# FPGAPower.net
KiCad netlist of a schematic drawn in Altium Designer
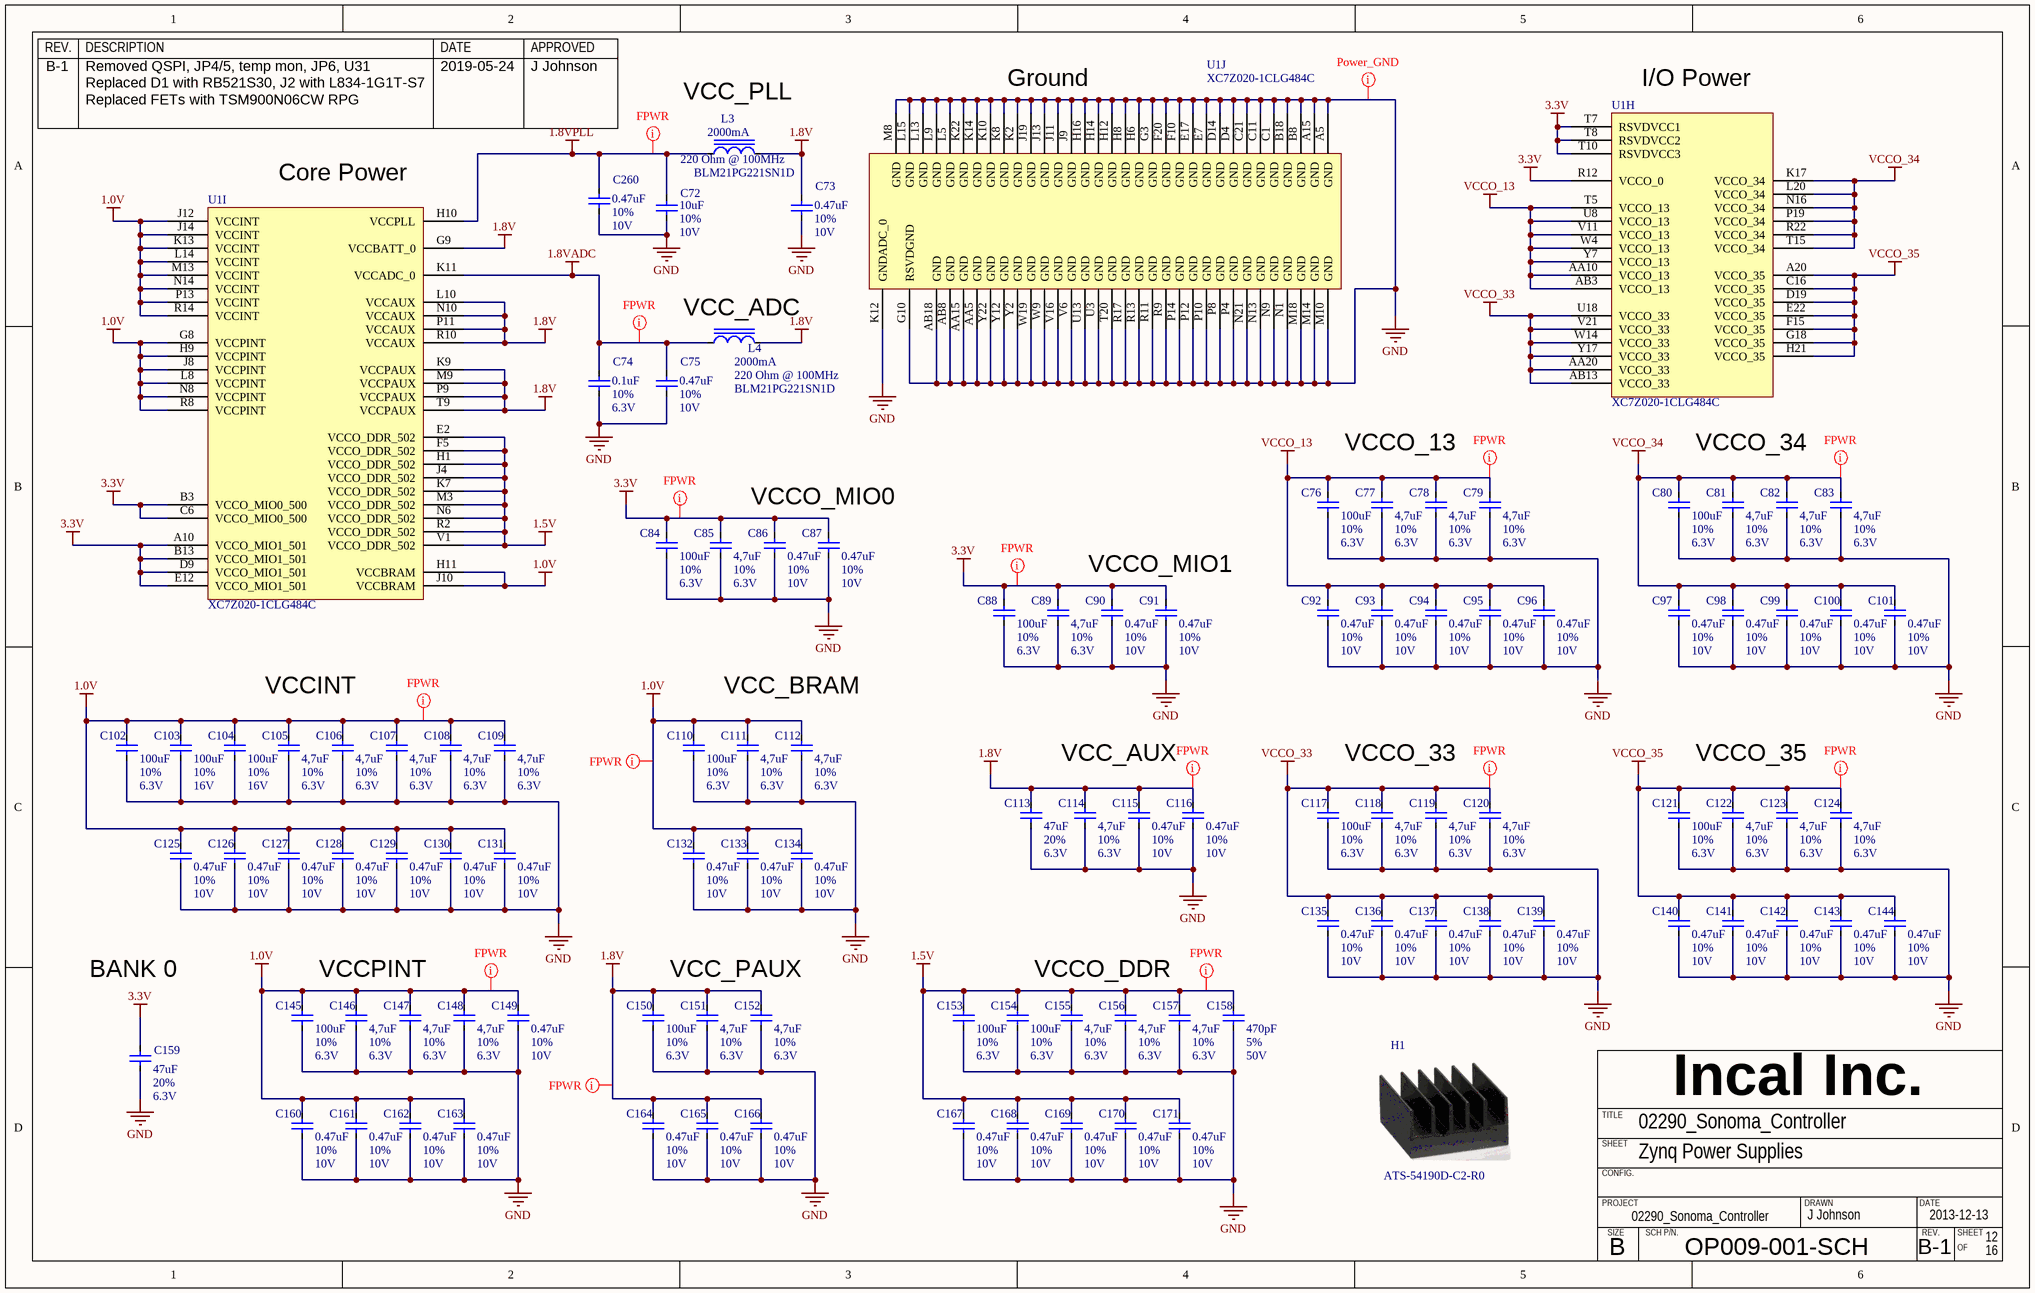
[diagram p0: FPGAPower.SchDoc]

(export (version "E")
  (design (tool "Eeschema 10.0.6"))
  (components
    (comp (ref "C72")
      (value "10uF")
      (footprint "CAPC1608X38N")
      (description "Capacitor ceramic, X5R, 10uF, 10V, 10%, -55 to +85 C, EIA0603")
      (fields
        (field (name "TOLERANCE") "10%")
        (field (name "VOLTAGE") "10V")
        (field (name "Comment") "CAPACITOR_NP_TYPE1")
      )
      (libsource (lib "parts") (part "CAPACITOR_NP_TYPE1"))
    )
    (comp (ref "C73")
      (value "0.47uF")
      (footprint "CAPC1005X55N")
      (description "Capacitor ceramic, X5R, 0.47uF, 10V, 10%, -55 to +85 C, EIA0402")
      (fields
        (field (name "TOLERANCE") "10%")
        (field (name "VOLTAGE") "10V")
        (field (name "Comment") "CAPACITOR_NP_TYPE1")
      )
      (libsource (lib "parts") (part "CAPACITOR_NP_TYPE1"))
    )
    (comp (ref "C74")
      (value "0.1uF")
      (footprint "CAPC0603X33N")
      (description "Capacitor ceramic, X5R, 0.1uF, 6.3V, 10%, -55 to +125 C, EIA0201")
      (fields
        (field (name "TOLERANCE") "10%")
        (field (name "VOLTAGE") "6.3V")
        (field (name "Comment") "CAPACITOR_NP_TYPE1")
      )
      (libsource (lib "parts") (part "CAPACITOR_NP_TYPE1"))
    )
    (comp (ref "C75")
      (value "0.47uF")
      (footprint "CAPC1005X55N")
      (description "Capacitor ceramic, X5R, 0.47uF, 10V, 10%, -55 to +85 C, EIA0402")
      (fields
        (field (name "TOLERANCE") "10%")
        (field (name "VOLTAGE") "10V")
        (field (name "Comment") "CAPACITOR_NP_TYPE1")
      )
      (libsource (lib "parts") (part "CAPACITOR_NP_TYPE1"))
    )
    (comp (ref "C76")
      (value "100uF")
      (footprint "CAPC3225X250N")
      (description "Capacitor ceramic, X5R, 100uF, 6.3V, 10%, -55 to +85 C, EIA1210")
      (fields
        (field (name "TOLERANCE") "10%")
        (field (name "VOLTAGE") "6.3V")
        (field (name "Comment") "CAPACITOR_NP_TYPE1")
      )
      (libsource (lib "parts") (part "CAPACITOR_NP_TYPE1"))
    )
    (comp (ref "C77")
      (value "4,7uF")
      (footprint "CAPC1005X33N")
      (description "Capacitor ceramic, X5R, 4,7uF, 6.3V, 10%, -55 to +85 C, EIA0402")
      (fields
        (field (name "TOLERANCE") "10%")
        (field (name "VOLTAGE") "6.3V")
        (field (name "Comment") "CAPACITOR_NP_TYPE1")
      )
      (libsource (lib "parts") (part "CAPACITOR_NP_TYPE1"))
    )
    (comp (ref "C78")
      (value "4,7uF")
      (footprint "CAPC1005X33N")
      (description "Capacitor ceramic, X5R, 4,7uF, 6.3V, 10%, -55 to +85 C, EIA0402")
      (fields
        (field (name "TOLERANCE") "10%")
        (field (name "VOLTAGE") "6.3V")
        (field (name "Comment") "CAPACITOR_NP_TYPE1")
      )
      (libsource (lib "parts") (part "CAPACITOR_NP_TYPE1"))
    )
    (comp (ref "C79")
      (value "4,7uF")
      (footprint "CAPC1005X33N")
      (description "Capacitor ceramic, X5R, 4,7uF, 6.3V, 10%, -55 to +85 C, EIA0402")
      (fields
        (field (name "TOLERANCE") "10%")
        (field (name "VOLTAGE") "6.3V")
        (field (name "Comment") "CAPACITOR_NP_TYPE1")
      )
      (libsource (lib "parts") (part "CAPACITOR_NP_TYPE1"))
    )
    (comp (ref "C80")
      (value "100uF")
      (footprint "CAPC3225X250N")
      (description "Capacitor ceramic, X5R, 100uF, 6.3V, 10%, -55 to +85 C, EIA1210")
      (fields
        (field (name "TOLERANCE") "10%")
        (field (name "VOLTAGE") "6.3V")
        (field (name "Comment") "CAPACITOR_NP_TYPE1")
      )
      (libsource (lib "parts") (part "CAPACITOR_NP_TYPE1"))
    )
    (comp (ref "C81")
      (value "4,7uF")
      (footprint "CAPC1005X33N")
      (description "Capacitor ceramic, X5R, 4,7uF, 6.3V, 10%, -55 to +85 C, EIA0402")
      (fields
        (field (name "TOLERANCE") "10%")
        (field (name "VOLTAGE") "6.3V")
        (field (name "Comment") "CAPACITOR_NP_TYPE1")
      )
      (libsource (lib "parts") (part "CAPACITOR_NP_TYPE1"))
    )
    (comp (ref "C82")
      (value "4,7uF")
      (footprint "CAPC1005X33N")
      (description "Capacitor ceramic, X5R, 4,7uF, 6.3V, 10%, -55 to +85 C, EIA0402")
      (fields
        (field (name "TOLERANCE") "10%")
        (field (name "VOLTAGE") "6.3V")
        (field (name "Comment") "CAPACITOR_NP_TYPE1")
      )
      (libsource (lib "parts") (part "CAPACITOR_NP_TYPE1"))
    )
    (comp (ref "C83")
      (value "4,7uF")
      (footprint "CAPC1005X33N")
      (description "Capacitor ceramic, X5R, 4,7uF, 6.3V, 10%, -55 to +85 C, EIA0402")
      (fields
        (field (name "TOLERANCE") "10%")
        (field (name "VOLTAGE") "6.3V")
        (field (name "Comment") "CAPACITOR_NP_TYPE1")
      )
      (libsource (lib "parts") (part "CAPACITOR_NP_TYPE1"))
    )
    (comp (ref "C84")
      (value "100uF")
      (footprint "CAPC3225X250N")
      (description "Capacitor ceramic, X5R, 100uF, 6.3V, 10%, -55 to +85 C, EIA1210")
      (fields
        (field (name "TOLERANCE") "10%")
        (field (name "VOLTAGE") "6.3V")
        (field (name "Comment") "CAPACITOR_NP_TYPE1")
      )
      (libsource (lib "parts") (part "CAPACITOR_NP_TYPE1"))
    )
    (comp (ref "C85")
      (value "4,7uF")
      (footprint "CAPC1005X33N")
      (description "Capacitor ceramic, X5R, 4,7uF, 6.3V, 10%, -55 to +85 C, EIA0402")
      (fields
        (field (name "TOLERANCE") "10%")
        (field (name "VOLTAGE") "6.3V")
        (field (name "Comment") "CAPACITOR_NP_TYPE1")
      )
      (libsource (lib "parts") (part "CAPACITOR_NP_TYPE1"))
    )
    (comp (ref "C86")
      (value "0.47uF")
      (footprint "CAPC1005X55N")
      (description "Capacitor ceramic, X5R, 0.47uF, 10V, 10%, -55 to +85 C, EIA0402")
      (fields
        (field (name "TOLERANCE") "10%")
        (field (name "VOLTAGE") "10V")
        (field (name "Comment") "CAPACITOR_NP_TYPE1")
      )
      (libsource (lib "parts") (part "CAPACITOR_NP_TYPE1"))
    )
    (comp (ref "C87")
      (value "0.47uF")
      (footprint "CAPC1005X55N")
      (description "Capacitor ceramic, X5R, 0.47uF, 10V, 10%, -55 to +85 C, EIA0402")
      (fields
        (field (name "TOLERANCE") "10%")
        (field (name "VOLTAGE") "10V")
        (field (name "Comment") "CAPACITOR_NP_TYPE1")
      )
      (libsource (lib "parts") (part "CAPACITOR_NP_TYPE1"))
    )
    (comp (ref "C88")
      (value "100uF")
      (footprint "CAPC3225X250N")
      (description "Capacitor ceramic, X5R, 100uF, 6.3V, 10%, -55 to +85 C, EIA1210")
      (fields
        (field (name "TOLERANCE") "10%")
        (field (name "VOLTAGE") "6.3V")
        (field (name "Comment") "CAPACITOR_NP_TYPE1")
      )
      (libsource (lib "parts") (part "CAPACITOR_NP_TYPE1"))
    )
    (comp (ref "C89")
      (value "4,7uF")
      (footprint "CAPC1005X33N")
      (description "Capacitor ceramic, X5R, 4,7uF, 6.3V, 10%, -55 to +85 C, EIA0402")
      (fields
        (field (name "TOLERANCE") "10%")
        (field (name "VOLTAGE") "6.3V")
        (field (name "Comment") "CAPACITOR_NP_TYPE1")
      )
      (libsource (lib "parts") (part "CAPACITOR_NP_TYPE1"))
    )
    (comp (ref "C90")
      (value "0.47uF")
      (footprint "CAPC1005X55N")
      (description "Capacitor ceramic, X5R, 0.47uF, 10V, 10%, -55 to +85 C, EIA0402")
      (fields
        (field (name "TOLERANCE") "10%")
        (field (name "VOLTAGE") "10V")
        (field (name "Comment") "CAPACITOR_NP_TYPE1")
      )
      (libsource (lib "parts") (part "CAPACITOR_NP_TYPE1"))
    )
    (comp (ref "C91")
      (value "0.47uF")
      (footprint "CAPC1005X55N")
      (description "Capacitor ceramic, X5R, 0.47uF, 10V, 10%, -55 to +85 C, EIA0402")
      (fields
        (field (name "TOLERANCE") "10%")
        (field (name "VOLTAGE") "10V")
        (field (name "Comment") "CAPACITOR_NP_TYPE1")
      )
      (libsource (lib "parts") (part "CAPACITOR_NP_TYPE1"))
    )
    (comp (ref "C92")
      (value "0.47uF")
      (footprint "CAPC1005X55N")
      (description "Capacitor ceramic, X5R, 0.47uF, 10V, 10%, -55 to +85 C, EIA0402")
      (fields
        (field (name "TOLERANCE") "10%")
        (field (name "VOLTAGE") "10V")
        (field (name "Comment") "CAPACITOR_NP_TYPE1")
      )
      (libsource (lib "parts") (part "CAPACITOR_NP_TYPE1"))
    )
    (comp (ref "C93")
      (value "0.47uF")
      (footprint "CAPC1005X55N")
      (description "Capacitor ceramic, X5R, 0.47uF, 10V, 10%, -55 to +85 C, EIA0402")
      (fields
        (field (name "TOLERANCE") "10%")
        (field (name "VOLTAGE") "10V")
        (field (name "Comment") "CAPACITOR_NP_TYPE1")
      )
      (libsource (lib "parts") (part "CAPACITOR_NP_TYPE1"))
    )
    (comp (ref "C94")
      (value "0.47uF")
      (footprint "CAPC1005X55N")
      (description "Capacitor ceramic, X5R, 0.47uF, 10V, 10%, -55 to +85 C, EIA0402")
      (fields
        (field (name "TOLERANCE") "10%")
        (field (name "VOLTAGE") "10V")
        (field (name "Comment") "CAPACITOR_NP_TYPE1")
      )
      (libsource (lib "parts") (part "CAPACITOR_NP_TYPE1"))
    )
    (comp (ref "C95")
      (value "0.47uF")
      (footprint "CAPC1005X55N")
      (description "Capacitor ceramic, X5R, 0.47uF, 10V, 10%, -55 to +85 C, EIA0402")
      (fields
        (field (name "TOLERANCE") "10%")
        (field (name "VOLTAGE") "10V")
        (field (name "Comment") "CAPACITOR_NP_TYPE1")
      )
      (libsource (lib "parts") (part "CAPACITOR_NP_TYPE1"))
    )
    (comp (ref "C96")
      (value "0.47uF")
      (footprint "CAPC1005X55N")
      (description "Capacitor ceramic, X5R, 0.47uF, 10V, 10%, -55 to +85 C, EIA0402")
      (fields
        (field (name "TOLERANCE") "10%")
        (field (name "VOLTAGE") "10V")
        (field (name "Comment") "CAPACITOR_NP_TYPE1")
      )
      (libsource (lib "parts") (part "CAPACITOR_NP_TYPE1"))
    )
    (comp (ref "C97")
      (value "0.47uF")
      (footprint "CAPC1005X55N")
      (description "Capacitor ceramic, X5R, 0.47uF, 10V, 10%, -55 to +85 C, EIA0402")
      (fields
        (field (name "TOLERANCE") "10%")
        (field (name "VOLTAGE") "10V")
        (field (name "Comment") "CAPACITOR_NP_TYPE1")
      )
      (libsource (lib "parts") (part "CAPACITOR_NP_TYPE1"))
    )
    (comp (ref "C98")
      (value "0.47uF")
      (footprint "CAPC1005X55N")
      (description "Capacitor ceramic, X5R, 0.47uF, 10V, 10%, -55 to +85 C, EIA0402")
      (fields
        (field (name "TOLERANCE") "10%")
        (field (name "VOLTAGE") "10V")
        (field (name "Comment") "CAPACITOR_NP_TYPE1")
      )
      (libsource (lib "parts") (part "CAPACITOR_NP_TYPE1"))
    )
    (comp (ref "C99")
      (value "0.47uF")
      (footprint "CAPC1005X55N")
      (description "Capacitor ceramic, X5R, 0.47uF, 10V, 10%, -55 to +85 C, EIA0402")
      (fields
        (field (name "TOLERANCE") "10%")
        (field (name "VOLTAGE") "10V")
        (field (name "Comment") "CAPACITOR_NP_TYPE1")
      )
      (libsource (lib "parts") (part "CAPACITOR_NP_TYPE1"))
    )
    (comp (ref "C100")
      (value "0.47uF")
      (footprint "CAPC1005X55N")
      (description "Capacitor ceramic, X5R, 0.47uF, 10V, 10%, -55 to +85 C, EIA0402")
      (fields
        (field (name "TOLERANCE") "10%")
        (field (name "VOLTAGE") "10V")
        (field (name "Comment") "CAPACITOR_NP_TYPE1")
      )
      (libsource (lib "parts") (part "CAPACITOR_NP_TYPE1"))
    )
    (comp (ref "C101")
      (value "0.47uF")
      (footprint "CAPC1005X55N")
      (description "Capacitor ceramic, X5R, 0.47uF, 10V, 10%, -55 to +85 C, EIA0402")
      (fields
        (field (name "TOLERANCE") "10%")
        (field (name "VOLTAGE") "10V")
        (field (name "Comment") "CAPACITOR_NP_TYPE1")
      )
      (libsource (lib "parts") (part "CAPACITOR_NP_TYPE1"))
    )
    (comp (ref "C102")
      (value "100uF")
      (footprint "CAPC3225X250N")
      (description "Capacitor ceramic, X5R, 100uF, 6.3V, 10%, -55 to +85 C, EIA1210")
      (fields
        (field (name "TOLERANCE") "10%")
        (field (name "VOLTAGE") "6.3V")
        (field (name "Comment") "CAPACITOR_NP_TYPE1")
      )
      (libsource (lib "parts") (part "CAPACITOR_NP_TYPE1"))
    )
    (comp (ref "C103")
      (value "100uF")
      (footprint "CAPC3225X250N")
      (description "Capacitor ceramic, X5R, 100uF, 16V, 10%, -55 to +85 C, EIA1210")
      (fields
        (field (name "TOLERANCE") "10%")
        (field (name "VOLTAGE") "16V")
        (field (name "Comment") "CAPACITOR_NP_TYPE1")
      )
      (libsource (lib "parts") (part "CAPACITOR_NP_TYPE1"))
    )
    (comp (ref "C104")
      (value "100uF")
      (footprint "CAPC3225X250N")
      (description "Capacitor ceramic, X5R, 100uF, 16V, 10%, -55 to +85 C, EIA1210")
      (fields
        (field (name "TOLERANCE") "10%")
        (field (name "VOLTAGE") "16V")
        (field (name "Comment") "CAPACITOR_NP_TYPE1")
      )
      (libsource (lib "parts") (part "CAPACITOR_NP_TYPE1"))
    )
    (comp (ref "C105")
      (value "4,7uF")
      (footprint "CAPC1005X33N")
      (description "Capacitor ceramic, X5R, 4,7uF, 6.3V, 10%, -55 to +85 C, EIA0402")
      (fields
        (field (name "TOLERANCE") "10%")
        (field (name "VOLTAGE") "6.3V")
        (field (name "Comment") "CAPACITOR_NP_TYPE1")
      )
      (libsource (lib "parts") (part "CAPACITOR_NP_TYPE1"))
    )
    (comp (ref "C106")
      (value "4,7uF")
      (footprint "CAPC1005X33N")
      (description "Capacitor ceramic, X5R, 4,7uF, 6.3V, 10%, -55 to +85 C, EIA0402")
      (fields
        (field (name "TOLERANCE") "10%")
        (field (name "VOLTAGE") "6.3V")
        (field (name "Comment") "CAPACITOR_NP_TYPE1")
      )
      (libsource (lib "parts") (part "CAPACITOR_NP_TYPE1"))
    )
    (comp (ref "C107")
      (value "4,7uF")
      (footprint "CAPC1005X33N")
      (description "Capacitor ceramic, X5R, 4,7uF, 6.3V, 10%, -55 to +85 C, EIA0402")
      (fields
        (field (name "TOLERANCE") "10%")
        (field (name "VOLTAGE") "6.3V")
        (field (name "Comment") "CAPACITOR_NP_TYPE1")
      )
      (libsource (lib "parts") (part "CAPACITOR_NP_TYPE1"))
    )
    (comp (ref "C108")
      (value "4,7uF")
      (footprint "CAPC1005X33N")
      (description "Capacitor ceramic, X5R, 4,7uF, 6.3V, 10%, -55 to +85 C, EIA0402")
      (fields
        (field (name "TOLERANCE") "10%")
        (field (name "VOLTAGE") "6.3V")
        (field (name "Comment") "CAPACITOR_NP_TYPE1")
      )
      (libsource (lib "parts") (part "CAPACITOR_NP_TYPE1"))
    )
    (comp (ref "C109")
      (value "4,7uF")
      (footprint "CAPC1005X33N")
      (description "Capacitor ceramic, X5R, 4,7uF, 6.3V, 10%, -55 to +85 C, EIA0402")
      (fields
        (field (name "TOLERANCE") "10%")
        (field (name "VOLTAGE") "6.3V")
        (field (name "Comment") "CAPACITOR_NP_TYPE1")
      )
      (libsource (lib "parts") (part "CAPACITOR_NP_TYPE1"))
    )
    (comp (ref "C110")
      (value "100uF")
      (footprint "CAPC3225X250N")
      (description "Capacitor ceramic, X5R, 100uF, 6.3V, 10%, -55 to +85 C, EIA1210")
      (fields
        (field (name "TOLERANCE") "10%")
        (field (name "VOLTAGE") "6.3V")
        (field (name "Comment") "CAPACITOR_NP_TYPE1")
      )
      (libsource (lib "parts") (part "CAPACITOR_NP_TYPE1"))
    )
    (comp (ref "C111")
      (value "4,7uF")
      (footprint "CAPC1005X33N")
      (description "Capacitor ceramic, X5R, 4,7uF, 6.3V, 10%, -55 to +85 C, EIA0402")
      (fields
        (field (name "TOLERANCE") "10%")
        (field (name "VOLTAGE") "6.3V")
        (field (name "Comment") "CAPACITOR_NP_TYPE1")
      )
      (libsource (lib "parts") (part "CAPACITOR_NP_TYPE1"))
    )
    (comp (ref "C112")
      (value "4,7uF")
      (footprint "CAPC1005X33N")
      (description "Capacitor ceramic, X5R, 4,7uF, 6.3V, 10%, -55 to +85 C, EIA0402")
      (fields
        (field (name "TOLERANCE") "10%")
        (field (name "VOLTAGE") "6.3V")
        (field (name "Comment") "CAPACITOR_NP_TYPE1")
      )
      (libsource (lib "parts") (part "CAPACITOR_NP_TYPE1"))
    )
    (comp (ref "C113")
      (value "47uF")
      (footprint "CAPC2013X125N")
      (description "Capacitor ceramic, X5R, 47uF, 6.3V, 20%, -55 to +85 C,")
      (fields
        (field (name "TOLERANCE") "20%")
        (field (name "VOLTAGE") "6.3V")
        (field (name "Comment") "CAPACITOR_NP_TYPE1")
      )
      (libsource (lib "parts") (part "CAPACITOR_NP_TYPE1"))
    )
    (comp (ref "C114")
      (value "4,7uF")
      (footprint "CAPC1005X33N")
      (description "Capacitor ceramic, X5R, 4,7uF, 6.3V, 10%, -55 to +85 C, EIA0402")
      (fields
        (field (name "TOLERANCE") "10%")
        (field (name "VOLTAGE") "6.3V")
        (field (name "Comment") "CAPACITOR_NP_TYPE1")
      )
      (libsource (lib "parts") (part "CAPACITOR_NP_TYPE1"))
    )
    (comp (ref "C115")
      (value "0.47uF")
      (footprint "CAPC1005X55N")
      (description "Capacitor ceramic, X5R, 0.47uF, 10V, 10%, -55 to +85 C, EIA0402")
      (fields
        (field (name "TOLERANCE") "10%")
        (field (name "VOLTAGE") "10V")
        (field (name "Comment") "CAPACITOR_NP_TYPE1")
      )
      (libsource (lib "parts") (part "CAPACITOR_NP_TYPE1"))
    )
    (comp (ref "C116")
      (value "0.47uF")
      (footprint "CAPC1005X55N")
      (description "Capacitor ceramic, X5R, 0.47uF, 10V, 10%, -55 to +85 C, EIA0402")
      (fields
        (field (name "TOLERANCE") "10%")
        (field (name "VOLTAGE") "10V")
        (field (name "Comment") "CAPACITOR_NP_TYPE1")
      )
      (libsource (lib "parts") (part "CAPACITOR_NP_TYPE1"))
    )
    (comp (ref "C117")
      (value "100uF")
      (footprint "CAPC3225X250N")
      (description "Capacitor ceramic, X5R, 100uF, 6.3V, 10%, -55 to +85 C, EIA1210")
      (fields
        (field (name "TOLERANCE") "10%")
        (field (name "VOLTAGE") "6.3V")
        (field (name "Comment") "CAPACITOR_NP_TYPE1")
      )
      (libsource (lib "parts") (part "CAPACITOR_NP_TYPE1"))
    )
    (comp (ref "C118")
      (value "4,7uF")
      (footprint "CAPC1005X33N")
      (description "Capacitor ceramic, X5R, 4,7uF, 6.3V, 10%, -55 to +85 C, EIA0402")
      (fields
        (field (name "TOLERANCE") "10%")
        (field (name "VOLTAGE") "6.3V")
        (field (name "Comment") "CAPACITOR_NP_TYPE1")
      )
      (libsource (lib "parts") (part "CAPACITOR_NP_TYPE1"))
    )
    (comp (ref "C119")
      (value "4,7uF")
      (footprint "CAPC1005X33N")
      (description "Capacitor ceramic, X5R, 4,7uF, 6.3V, 10%, -55 to +85 C, EIA0402")
      (fields
        (field (name "TOLERANCE") "10%")
        (field (name "VOLTAGE") "6.3V")
        (field (name "Comment") "CAPACITOR_NP_TYPE1")
      )
      (libsource (lib "parts") (part "CAPACITOR_NP_TYPE1"))
    )
    (comp (ref "C120")
      (value "4,7uF")
      (footprint "CAPC1005X33N")
      (description "Capacitor ceramic, X5R, 4,7uF, 6.3V, 10%, -55 to +85 C, EIA0402")
      (fields
        (field (name "TOLERANCE") "10%")
        (field (name "VOLTAGE") "6.3V")
        (field (name "Comment") "CAPACITOR_NP_TYPE1")
      )
      (libsource (lib "parts") (part "CAPACITOR_NP_TYPE1"))
    )
    (comp (ref "C121")
      (value "100uF")
      (footprint "CAPC3225X250N")
      (description "Capacitor ceramic, X5R, 100uF, 6.3V, 10%, -55 to +85 C, EIA1210")
      (fields
        (field (name "TOLERANCE") "10%")
        (field (name "VOLTAGE") "6.3V")
        (field (name "Comment") "CAPACITOR_NP_TYPE1")
      )
      (libsource (lib "parts") (part "CAPACITOR_NP_TYPE1"))
    )
    (comp (ref "C122")
      (value "4,7uF")
      (footprint "CAPC1005X33N")
      (description "Capacitor ceramic, X5R, 4,7uF, 6.3V, 10%, -55 to +85 C, EIA0402")
      (fields
        (field (name "TOLERANCE") "10%")
        (field (name "VOLTAGE") "6.3V")
        (field (name "Comment") "CAPACITOR_NP_TYPE1")
      )
      (libsource (lib "parts") (part "CAPACITOR_NP_TYPE1"))
    )
    (comp (ref "C123")
      (value "4,7uF")
      (footprint "CAPC1005X33N")
      (description "Capacitor ceramic, X5R, 4,7uF, 6.3V, 10%, -55 to +85 C, EIA0402")
      (fields
        (field (name "TOLERANCE") "10%")
        (field (name "VOLTAGE") "6.3V")
        (field (name "Comment") "CAPACITOR_NP_TYPE1")
      )
      (libsource (lib "parts") (part "CAPACITOR_NP_TYPE1"))
    )
    (comp (ref "C124")
      (value "4,7uF")
      (footprint "CAPC1005X33N")
      (description "Capacitor ceramic, X5R, 4,7uF, 6.3V, 10%, -55 to +85 C, EIA0402")
      (fields
        (field (name "TOLERANCE") "10%")
        (field (name "VOLTAGE") "6.3V")
        (field (name "Comment") "CAPACITOR_NP_TYPE1")
      )
      (libsource (lib "parts") (part "CAPACITOR_NP_TYPE1"))
    )
    (comp (ref "C125")
      (value "0.47uF")
      (footprint "CAPC1005X55N")
      (description "Capacitor ceramic, X5R, 0.47uF, 10V, 10%, -55 to +85 C, EIA0402")
      (fields
        (field (name "TOLERANCE") "10%")
        (field (name "VOLTAGE") "10V")
        (field (name "Comment") "CAPACITOR_NP_TYPE1")
      )
      (libsource (lib "parts") (part "CAPACITOR_NP_TYPE1"))
    )
    (comp (ref "C126")
      (value "0.47uF")
      (footprint "CAPC1005X55N")
      (description "Capacitor ceramic, X5R, 0.47uF, 10V, 10%, -55 to +85 C, EIA0402")
      (fields
        (field (name "TOLERANCE") "10%")
        (field (name "VOLTAGE") "10V")
        (field (name "Comment") "CAPACITOR_NP_TYPE1")
      )
      (libsource (lib "parts") (part "CAPACITOR_NP_TYPE1"))
    )
    (comp (ref "C127")
      (value "0.47uF")
      (footprint "CAPC1005X55N")
      (description "Capacitor ceramic, X5R, 0.47uF, 10V, 10%, -55 to +85 C, EIA0402")
      (fields
        (field (name "TOLERANCE") "10%")
        (field (name "VOLTAGE") "10V")
        (field (name "Comment") "CAPACITOR_NP_TYPE1")
      )
      (libsource (lib "parts") (part "CAPACITOR_NP_TYPE1"))
    )
    (comp (ref "C128")
      (value "0.47uF")
      (footprint "CAPC1005X55N")
      (description "Capacitor ceramic, X5R, 0.47uF, 10V, 10%, -55 to +85 C, EIA0402")
      (fields
        (field (name "TOLERANCE") "10%")
        (field (name "VOLTAGE") "10V")
        (field (name "Comment") "CAPACITOR_NP_TYPE1")
      )
      (libsource (lib "parts") (part "CAPACITOR_NP_TYPE1"))
    )
    (comp (ref "C129")
      (value "0.47uF")
      (footprint "CAPC1005X55N")
      (description "Capacitor ceramic, X5R, 0.47uF, 10V, 10%, -55 to +85 C, EIA0402")
      (fields
        (field (name "TOLERANCE") "10%")
        (field (name "VOLTAGE") "10V")
        (field (name "Comment") "CAPACITOR_NP_TYPE1")
      )
      (libsource (lib "parts") (part "CAPACITOR_NP_TYPE1"))
    )
    (comp (ref "C130")
      (value "0.47uF")
      (footprint "CAPC1005X55N")
      (description "Capacitor ceramic, X5R, 0.47uF, 10V, 10%, -55 to +85 C, EIA0402")
      (fields
        (field (name "TOLERANCE") "10%")
        (field (name "VOLTAGE") "10V")
        (field (name "Comment") "CAPACITOR_NP_TYPE1")
      )
      (libsource (lib "parts") (part "CAPACITOR_NP_TYPE1"))
    )
    (comp (ref "C131")
      (value "0.47uF")
      (footprint "CAPC1005X55N")
      (description "Capacitor ceramic, X5R, 0.47uF, 10V, 10%, -55 to +85 C, EIA0402")
      (fields
        (field (name "TOLERANCE") "10%")
        (field (name "VOLTAGE") "10V")
        (field (name "Comment") "CAPACITOR_NP_TYPE1")
      )
      (libsource (lib "parts") (part "CAPACITOR_NP_TYPE1"))
    )
    (comp (ref "C132")
      (value "0.47uF")
      (footprint "CAPC1005X55N")
      (description "Capacitor ceramic, X5R, 0.47uF, 10V, 10%, -55 to +85 C, EIA0402")
      (fields
        (field (name "TOLERANCE") "10%")
        (field (name "VOLTAGE") "10V")
        (field (name "Comment") "CAPACITOR_NP_TYPE1")
      )
      (libsource (lib "parts") (part "CAPACITOR_NP_TYPE1"))
    )
    (comp (ref "C133")
      (value "0.47uF")
      (footprint "CAPC1005X55N")
      (description "Capacitor ceramic, X5R, 0.47uF, 10V, 10%, -55 to +85 C, EIA0402")
      (fields
        (field (name "TOLERANCE") "10%")
        (field (name "VOLTAGE") "10V")
        (field (name "Comment") "CAPACITOR_NP_TYPE1")
      )
      (libsource (lib "parts") (part "CAPACITOR_NP_TYPE1"))
    )
    (comp (ref "C134")
      (value "0.47uF")
      (footprint "CAPC1005X55N")
      (description "Capacitor ceramic, X5R, 0.47uF, 10V, 10%, -55 to +85 C, EIA0402")
      (fields
        (field (name "TOLERANCE") "10%")
        (field (name "VOLTAGE") "10V")
        (field (name "Comment") "CAPACITOR_NP_TYPE1")
      )
      (libsource (lib "parts") (part "CAPACITOR_NP_TYPE1"))
    )
    (comp (ref "C135")
      (value "0.47uF")
      (footprint "CAPC1005X55N")
      (description "Capacitor ceramic, X5R, 0.47uF, 10V, 10%, -55 to +85 C, EIA0402")
      (fields
        (field (name "TOLERANCE") "10%")
        (field (name "VOLTAGE") "10V")
        (field (name "Comment") "CAPACITOR_NP_TYPE1")
      )
      (libsource (lib "parts") (part "CAPACITOR_NP_TYPE1"))
    )
    (comp (ref "C136")
      (value "0.47uF")
      (footprint "CAPC1005X55N")
      (description "Capacitor ceramic, X5R, 0.47uF, 10V, 10%, -55 to +85 C, EIA0402")
      (fields
        (field (name "TOLERANCE") "10%")
        (field (name "VOLTAGE") "10V")
        (field (name "Comment") "CAPACITOR_NP_TYPE1")
      )
      (libsource (lib "parts") (part "CAPACITOR_NP_TYPE1"))
    )
    (comp (ref "C137")
      (value "0.47uF")
      (footprint "CAPC1005X55N")
      (description "Capacitor ceramic, X5R, 0.47uF, 10V, 10%, -55 to +85 C, EIA0402")
      (fields
        (field (name "TOLERANCE") "10%")
        (field (name "VOLTAGE") "10V")
        (field (name "Comment") "CAPACITOR_NP_TYPE1")
      )
      (libsource (lib "parts") (part "CAPACITOR_NP_TYPE1"))
    )
    (comp (ref "C138")
      (value "0.47uF")
      (footprint "CAPC1005X55N")
      (description "Capacitor ceramic, X5R, 0.47uF, 10V, 10%, -55 to +85 C, EIA0402")
      (fields
        (field (name "TOLERANCE") "10%")
        (field (name "VOLTAGE") "10V")
        (field (name "Comment") "CAPACITOR_NP_TYPE1")
      )
      (libsource (lib "parts") (part "CAPACITOR_NP_TYPE1"))
    )
    (comp (ref "C139")
      (value "0.47uF")
      (footprint "CAPC1005X55N")
      (description "Capacitor ceramic, X5R, 0.47uF, 10V, 10%, -55 to +85 C, EIA0402")
      (fields
        (field (name "TOLERANCE") "10%")
        (field (name "VOLTAGE") "10V")
        (field (name "Comment") "CAPACITOR_NP_TYPE1")
      )
      (libsource (lib "parts") (part "CAPACITOR_NP_TYPE1"))
    )
    (comp (ref "C140")
      (value "0.47uF")
      (footprint "CAPC1005X55N")
      (description "Capacitor ceramic, X5R, 0.47uF, 10V, 10%, -55 to +85 C, EIA0402")
      (fields
        (field (name "TOLERANCE") "10%")
        (field (name "VOLTAGE") "10V")
        (field (name "Comment") "CAPACITOR_NP_TYPE1")
      )
      (libsource (lib "parts") (part "CAPACITOR_NP_TYPE1"))
    )
    (comp (ref "C141")
      (value "0.47uF")
      (footprint "CAPC1005X55N")
      (description "Capacitor ceramic, X5R, 0.47uF, 10V, 10%, -55 to +85 C, EIA0402")
      (fields
        (field (name "TOLERANCE") "10%")
        (field (name "VOLTAGE") "10V")
        (field (name "Comment") "CAPACITOR_NP_TYPE1")
      )
      (libsource (lib "parts") (part "CAPACITOR_NP_TYPE1"))
    )
    (comp (ref "C142")
      (value "0.47uF")
      (footprint "CAPC1005X55N")
      (description "Capacitor ceramic, X5R, 0.47uF, 10V, 10%, -55 to +85 C, EIA0402")
      (fields
        (field (name "TOLERANCE") "10%")
        (field (name "VOLTAGE") "10V")
        (field (name "Comment") "CAPACITOR_NP_TYPE1")
      )
      (libsource (lib "parts") (part "CAPACITOR_NP_TYPE1"))
    )
    (comp (ref "C143")
      (value "0.47uF")
      (footprint "CAPC1005X55N")
      (description "Capacitor ceramic, X5R, 0.47uF, 10V, 10%, -55 to +85 C, EIA0402")
      (fields
        (field (name "TOLERANCE") "10%")
        (field (name "VOLTAGE") "10V")
        (field (name "Comment") "CAPACITOR_NP_TYPE1")
      )
      (libsource (lib "parts") (part "CAPACITOR_NP_TYPE1"))
    )
    (comp (ref "C144")
      (value "0.47uF")
      (footprint "CAPC1005X55N")
      (description "Capacitor ceramic, X5R, 0.47uF, 10V, 10%, -55 to +85 C, EIA0402")
      (fields
        (field (name "TOLERANCE") "10%")
        (field (name "VOLTAGE") "10V")
        (field (name "Comment") "CAPACITOR_NP_TYPE1")
      )
      (libsource (lib "parts") (part "CAPACITOR_NP_TYPE1"))
    )
    (comp (ref "C145")
      (value "100uF")
      (footprint "CAPC3225X250N")
      (description "Capacitor ceramic, X5R, 100uF, 6.3V, 10%, -55 to +85 C, EIA1210")
      (fields
        (field (name "TOLERANCE") "10%")
        (field (name "VOLTAGE") "6.3V")
        (field (name "Comment") "CAPACITOR_NP_TYPE1")
      )
      (libsource (lib "parts") (part "CAPACITOR_NP_TYPE1"))
    )
    (comp (ref "C146")
      (value "4,7uF")
      (footprint "CAPC1005X33N")
      (description "Capacitor ceramic, X5R, 4,7uF, 6.3V, 10%, -55 to +85 C, EIA0402")
      (fields
        (field (name "TOLERANCE") "10%")
        (field (name "VOLTAGE") "6.3V")
        (field (name "Comment") "CAPACITOR_NP_TYPE1")
      )
      (libsource (lib "parts") (part "CAPACITOR_NP_TYPE1"))
    )
    (comp (ref "C147")
      (value "4,7uF")
      (footprint "CAPC1005X33N")
      (description "Capacitor ceramic, X5R, 4,7uF, 6.3V, 10%, -55 to +85 C, EIA0402")
      (fields
        (field (name "TOLERANCE") "10%")
        (field (name "VOLTAGE") "6.3V")
        (field (name "Comment") "CAPACITOR_NP_TYPE1")
      )
      (libsource (lib "parts") (part "CAPACITOR_NP_TYPE1"))
    )
    (comp (ref "C148")
      (value "4,7uF")
      (footprint "CAPC1005X33N")
      (description "Capacitor ceramic, X5R, 4,7uF, 6.3V, 10%, -55 to +85 C, EIA0402")
      (fields
        (field (name "TOLERANCE") "10%")
        (field (name "VOLTAGE") "6.3V")
        (field (name "Comment") "CAPACITOR_NP_TYPE1")
      )
      (libsource (lib "parts") (part "CAPACITOR_NP_TYPE1"))
    )
    (comp (ref "C149")
      (value "0.47uF")
      (footprint "CAPC1005X55N")
      (description "Capacitor ceramic, X5R, 0.47uF, 10V, 10%, -55 to +85 C, EIA0402")
      (fields
        (field (name "TOLERANCE") "10%")
        (field (name "VOLTAGE") "10V")
        (field (name "Comment") "CAPACITOR_NP_TYPE1")
      )
      (libsource (lib "parts") (part "CAPACITOR_NP_TYPE1"))
    )
    (comp (ref "C150")
      (value "100uF")
      (footprint "CAPC3225X250N")
      (description "Capacitor ceramic, X5R, 100uF, 6.3V, 10%, -55 to +85 C, EIA1210")
      (fields
        (field (name "TOLERANCE") "10%")
        (field (name "VOLTAGE") "6.3V")
        (field (name "Comment") "CAPACITOR_NP_TYPE1")
      )
      (libsource (lib "parts") (part "CAPACITOR_NP_TYPE1"))
    )
    (comp (ref "C151")
      (value "4,7uF")
      (footprint "CAPC1005X33N")
      (description "Capacitor ceramic, X5R, 4,7uF, 6.3V, 10%, -55 to +85 C, EIA0402")
      (fields
        (field (name "TOLERANCE") "10%")
        (field (name "VOLTAGE") "6.3V")
        (field (name "Comment") "CAPACITOR_NP_TYPE1")
      )
      (libsource (lib "parts") (part "CAPACITOR_NP_TYPE1"))
    )
    (comp (ref "C152")
      (value "4,7uF")
      (footprint "CAPC1005X33N")
      (description "Capacitor ceramic, X5R, 4,7uF, 6.3V, 10%, -55 to +85 C, EIA0402")
      (fields
        (field (name "TOLERANCE") "10%")
        (field (name "VOLTAGE") "6.3V")
        (field (name "Comment") "CAPACITOR_NP_TYPE1")
      )
      (libsource (lib "parts") (part "CAPACITOR_NP_TYPE1"))
    )
    (comp (ref "C153")
      (value "100uF")
      (footprint "CAPC3225X250N")
      (description "Capacitor ceramic, X5R, 100uF, 6.3V, 10%, -55 to +85 C, EIA1210")
      (fields
        (field (name "TOLERANCE") "10%")
        (field (name "VOLTAGE") "6.3V")
        (field (name "Comment") "CAPACITOR_NP_TYPE1")
      )
      (libsource (lib "parts") (part "CAPACITOR_NP_TYPE1"))
    )
    (comp (ref "C154")
      (value "100uF")
      (footprint "CAPC3225X250N")
      (description "Capacitor ceramic, X5R, 100uF, 6.3V, 10%, -55 to +85 C, EIA1210")
      (fields
        (field (name "TOLERANCE") "10%")
        (field (name "VOLTAGE") "6.3V")
        (field (name "Comment") "CAPACITOR_NP_TYPE1")
      )
      (libsource (lib "parts") (part "CAPACITOR_NP_TYPE1"))
    )
    (comp (ref "C155")
      (value "4,7uF")
      (footprint "CAPC1005X33N")
      (description "Capacitor ceramic, X5R, 4,7uF, 6.3V, 10%, -55 to +85 C, EIA0402")
      (fields
        (field (name "TOLERANCE") "10%")
        (field (name "VOLTAGE") "6.3V")
        (field (name "Comment") "CAPACITOR_NP_TYPE1")
      )
      (libsource (lib "parts") (part "CAPACITOR_NP_TYPE1"))
    )
    (comp (ref "C156")
      (value "4,7uF")
      (footprint "CAPC1005X33N")
      (description "Capacitor ceramic, X5R, 4,7uF, 6.3V, 10%, -55 to +85 C, EIA0402")
      (fields
        (field (name "TOLERANCE") "10%")
        (field (name "VOLTAGE") "6.3V")
        (field (name "Comment") "CAPACITOR_NP_TYPE1")
      )
      (libsource (lib "parts") (part "CAPACITOR_NP_TYPE1"))
    )
    (comp (ref "C157")
      (value "4,7uF")
      (footprint "CAPC1005X33N")
      (description "Capacitor ceramic, X5R, 4,7uF, 6.3V, 10%, -55 to +85 C, EIA0402")
      (fields
        (field (name "TOLERANCE") "10%")
        (field (name "VOLTAGE") "6.3V")
        (field (name "Comment") "CAPACITOR_NP_TYPE1")
      )
      (libsource (lib "parts") (part "CAPACITOR_NP_TYPE1"))
    )
    (comp (ref "C158")
      (value "470pF")
      (footprint "CAPC1005X33N")
      (description "Capacitor ceramic, C0G (NP0), 470pF, 50V, 5%, -55 to +125 C, EIA0402")
      (fields
        (field (name "TOLERANCE") "5%")
        (field (name "VOLTAGE") "50V")
        (field (name "Comment") "CAPACITOR_NP_TYPE1")
      )
      (libsource (lib "parts") (part "CAPACITOR_NP_TYPE1"))
    )
    (comp (ref "C159")
      (value "47uF")
      (footprint "CAPC2013X125N")
      (description "Capacitor ceramic, X5R, 47uF, 6.3V, 20%, -55 to +85 C,")
      (fields
        (field (name "TOLERANCE") "20%")
        (field (name "VOLTAGE") "6.3V")
        (field (name "Comment") "CAPACITOR_NP_TYPE1")
      )
      (libsource (lib "parts") (part "CAPACITOR_NP_TYPE1"))
    )
    (comp (ref "C160")
      (value "0.47uF")
      (footprint "CAPC1005X55N")
      (description "Capacitor ceramic, X5R, 0.47uF, 10V, 10%, -55 to +85 C, EIA0402")
      (fields
        (field (name "TOLERANCE") "10%")
        (field (name "VOLTAGE") "10V")
        (field (name "Comment") "CAPACITOR_NP_TYPE1")
      )
      (libsource (lib "parts") (part "CAPACITOR_NP_TYPE1"))
    )
    (comp (ref "C161")
      (value "0.47uF")
      (footprint "CAPC1005X55N")
      (description "Capacitor ceramic, X5R, 0.47uF, 10V, 10%, -55 to +85 C, EIA0402")
      (fields
        (field (name "TOLERANCE") "10%")
        (field (name "VOLTAGE") "10V")
        (field (name "Comment") "CAPACITOR_NP_TYPE1")
      )
      (libsource (lib "parts") (part "CAPACITOR_NP_TYPE1"))
    )
    (comp (ref "C162")
      (value "0.47uF")
      (footprint "CAPC1005X55N")
      (description "Capacitor ceramic, X5R, 0.47uF, 10V, 10%, -55 to +85 C, EIA0402")
      (fields
        (field (name "TOLERANCE") "10%")
        (field (name "VOLTAGE") "10V")
        (field (name "Comment") "CAPACITOR_NP_TYPE1")
      )
      (libsource (lib "parts") (part "CAPACITOR_NP_TYPE1"))
    )
    (comp (ref "C163")
      (value "0.47uF")
      (footprint "CAPC1005X55N")
      (description "Capacitor ceramic, X5R, 0.47uF, 10V, 10%, -55 to +85 C, EIA0402")
      (fields
        (field (name "TOLERANCE") "10%")
        (field (name "VOLTAGE") "10V")
        (field (name "Comment") "CAPACITOR_NP_TYPE1")
      )
      (libsource (lib "parts") (part "CAPACITOR_NP_TYPE1"))
    )
    (comp (ref "C164")
      (value "0.47uF")
      (footprint "CAPC1005X55N")
      (description "Capacitor ceramic, X5R, 0.47uF, 10V, 10%, -55 to +85 C, EIA0402")
      (fields
        (field (name "TOLERANCE") "10%")
        (field (name "VOLTAGE") "10V")
        (field (name "Comment") "CAPACITOR_NP_TYPE1")
      )
      (libsource (lib "parts") (part "CAPACITOR_NP_TYPE1"))
    )
    (comp (ref "C165")
      (value "0.47uF")
      (footprint "CAPC1005X55N")
      (description "Capacitor ceramic, X5R, 0.47uF, 10V, 10%, -55 to +85 C, EIA0402")
      (fields
        (field (name "TOLERANCE") "10%")
        (field (name "VOLTAGE") "10V")
        (field (name "Comment") "CAPACITOR_NP_TYPE1")
      )
      (libsource (lib "parts") (part "CAPACITOR_NP_TYPE1"))
    )
    (comp (ref "C166")
      (value "0.47uF")
      (footprint "CAPC1005X55N")
      (description "Capacitor ceramic, X5R, 0.47uF, 10V, 10%, -55 to +85 C, EIA0402")
      (fields
        (field (name "TOLERANCE") "10%")
        (field (name "VOLTAGE") "10V")
        (field (name "Comment") "CAPACITOR_NP_TYPE1")
      )
      (libsource (lib "parts") (part "CAPACITOR_NP_TYPE1"))
    )
    (comp (ref "C167")
      (value "0.47uF")
      (footprint "CAPC1005X55N")
      (description "Capacitor ceramic, X5R, 0.47uF, 10V, 10%, -55 to +85 C, EIA0402")
      (fields
        (field (name "TOLERANCE") "10%")
        (field (name "VOLTAGE") "10V")
        (field (name "Comment") "CAPACITOR_NP_TYPE1")
      )
      (libsource (lib "parts") (part "CAPACITOR_NP_TYPE1"))
    )
    (comp (ref "C168")
      (value "0.47uF")
      (footprint "CAPC1005X55N")
      (description "Capacitor ceramic, X5R, 0.47uF, 10V, 10%, -55 to +85 C, EIA0402")
      (fields
        (field (name "TOLERANCE") "10%")
        (field (name "VOLTAGE") "10V")
        (field (name "Comment") "CAPACITOR_NP_TYPE1")
      )
      (libsource (lib "parts") (part "CAPACITOR_NP_TYPE1"))
    )
    (comp (ref "C169")
      (value "0.47uF")
      (footprint "CAPC1005X55N")
      (description "Capacitor ceramic, X5R, 0.47uF, 10V, 10%, -55 to +85 C, EIA0402")
      (fields
        (field (name "TOLERANCE") "10%")
        (field (name "VOLTAGE") "10V")
        (field (name "Comment") "CAPACITOR_NP_TYPE1")
      )
      (libsource (lib "parts") (part "CAPACITOR_NP_TYPE1"))
    )
    (comp (ref "C170")
      (value "0.47uF")
      (footprint "CAPC1005X55N")
      (description "Capacitor ceramic, X5R, 0.47uF, 10V, 10%, -55 to +85 C, EIA0402")
      (fields
        (field (name "TOLERANCE") "10%")
        (field (name "VOLTAGE") "10V")
        (field (name "Comment") "CAPACITOR_NP_TYPE1")
      )
      (libsource (lib "parts") (part "CAPACITOR_NP_TYPE1"))
    )
    (comp (ref "C171")
      (value "0.47uF")
      (footprint "CAPC1005X55N")
      (description "Capacitor ceramic, X5R, 0.47uF, 10V, 10%, -55 to +85 C, EIA0402")
      (fields
        (field (name "TOLERANCE") "10%")
        (field (name "VOLTAGE") "10V")
        (field (name "Comment") "CAPACITOR_NP_TYPE1")
      )
      (libsource (lib "parts") (part "CAPACITOR_NP_TYPE1"))
    )
    (comp (ref "C260")
      (value "0.47uF")
      (footprint "CAPC1005X55N")
      (description "Capacitor ceramic, X5R, 0.47uF, 10V, 10%, -55 to +85 C, EIA0402")
      (fields
        (field (name "TOLERANCE") "10%")
        (field (name "VOLTAGE") "10V")
        (field (name "Comment") "CAPACITOR_NP_TYPE1")
      )
      (libsource (lib "parts") (part "CAPACITOR_NP_TYPE1"))
    )
    (comp (ref "H1")
      (value "ATS-54190D-C2-R0")
      (description "Heat Sink BGA, 19x19x9.5mm, Adhesive")
      (fields
        (field (name "POWER") "Pow")
        (field (name "VOLTAGE") "Vol")
        (field (name "MFG PART NUMBER 1") "ATS-54190D-C2-R0")
      )
      (libsource (lib "parts") (part "ATS-54190D-C2-R0"))
    )
    (comp (ref "L3")
      (value "220 Ohm @ 100MHz")
      (footprint "INDC2012X85N")
      (description "Ferrite chip, 220 Ohm @ 100MHz, 2000mA, 25%, -55 to +125 C, 0805")
      (fields
        (field (name "TOLERANCE") "25%")
        (field (name "CURRENT") "2000mA")
        (field (name "MFG PART NUMBER 1") "BLM21PG221SN1D")
        (field (name "Comment") "INDUCTOR_CORE_TYPE1")
      )
      (libsource (lib "parts") (part "INDUCTOR_CORE_TYPE1"))
    )
    (comp (ref "L4")
      (value "220 Ohm @ 100MHz")
      (footprint "INDC2012X85N")
      (description "Ferrite chip, 220 Ohm @ 100MHz, 2000mA, 25%, -55 to +125 C, 0805")
      (fields
        (field (name "TOLERANCE") "25%")
        (field (name "CURRENT") "2000mA")
        (field (name "MFG PART NUMBER 1") "BLM21PG221SN1D")
        (field (name "Comment") "INDUCTOR_CORE_TYPE1")
      )
      (libsource (lib "parts") (part "INDUCTOR_CORE_TYPE1"))
    )
    (comp (ref "U1")
      (value "XC7Z020-1CLG484C")
      (footprint "CLG484")
      (description "667 MHz Zynq™-7000 AP SoC, 130 PS I/O, 200 FPGA I/O, 484-Ball BGA, Speed Grade 1, Commercial Grade")
      (fields (field (name "GENERIC PART NUMBER") "XC7Z020") (field (name "MANUFACTURER") "Xilinx"))
      (libsource (lib "parts") (part "XC7Z020-1CLG484C"))
    )
  )
  (nets
    (net (code "1") (name "1.0V") (class "Default")
      (node (ref "C102") (pin "1") (pinfunction "1_1") (pintype "passive"))
      (node (ref "C103") (pin "1") (pinfunction "1_1") (pintype "passive"))
      (node (ref "C104") (pin "1") (pinfunction "1_1") (pintype "passive"))
      (node (ref "C105") (pin "1") (pinfunction "1_1") (pintype "passive"))
      (node (ref "C106") (pin "1") (pinfunction "1_1") (pintype "passive"))
      (node (ref "C107") (pin "1") (pinfunction "1_1") (pintype "passive"))
      (node (ref "C108") (pin "1") (pinfunction "1_1") (pintype "passive"))
      (node (ref "C109") (pin "1") (pinfunction "1_1") (pintype "passive"))
      (node (ref "C110") (pin "1") (pinfunction "1_1") (pintype "passive"))
      (node (ref "C111") (pin "1") (pinfunction "1_1") (pintype "passive"))
      (node (ref "C112") (pin "1") (pinfunction "1_1") (pintype "passive"))
      (node (ref "C125") (pin "1") (pinfunction "1_1") (pintype "passive"))
      (node (ref "C126") (pin "1") (pinfunction "1_1") (pintype "passive"))
      (node (ref "C127") (pin "1") (pinfunction "1_1") (pintype "passive"))
      (node (ref "C128") (pin "1") (pinfunction "1_1") (pintype "passive"))
      (node (ref "C129") (pin "1") (pinfunction "1_1") (pintype "passive"))
      (node (ref "C130") (pin "1") (pinfunction "1_1") (pintype "passive"))
      (node (ref "C131") (pin "1") (pinfunction "1_1") (pintype "passive"))
      (node (ref "C132") (pin "1") (pinfunction "1_1") (pintype "passive"))
      (node (ref "C133") (pin "1") (pinfunction "1_1") (pintype "passive"))
      (node (ref "C134") (pin "1") (pinfunction "1_1") (pintype "passive"))
      (node (ref "C145") (pin "1") (pinfunction "1_1") (pintype "passive"))
      (node (ref "C146") (pin "1") (pinfunction "1_1") (pintype "passive"))
      (node (ref "C147") (pin "1") (pinfunction "1_1") (pintype "passive"))
      (node (ref "C148") (pin "1") (pinfunction "1_1") (pintype "passive"))
      (node (ref "C149") (pin "1") (pinfunction "1_1") (pintype "passive"))
      (node (ref "C160") (pin "1") (pinfunction "1_1") (pintype "passive"))
      (node (ref "C161") (pin "1") (pinfunction "1_1") (pintype "passive"))
      (node (ref "C162") (pin "1") (pinfunction "1_1") (pintype "passive"))
      (node (ref "C163") (pin "1") (pinfunction "1_1") (pintype "passive"))
      (node (ref "U1") (pin "G8") (pinfunction "VCCPINT_G8") (pintype "power_in"))
      (node (ref "U1") (pin "H11") (pinfunction "VCCBRAM_H11") (pintype "power_in"))
      (node (ref "U1") (pin "H9") (pinfunction "VCCPINT_H9") (pintype "power_in"))
      (node (ref "U1") (pin "J10") (pinfunction "VCCBRAM_J10") (pintype "power_in"))
      (node (ref "U1") (pin "J12") (pinfunction "VCCINT_J12") (pintype "power_in"))
      (node (ref "U1") (pin "J14") (pinfunction "VCCINT_J14") (pintype "power_in"))
      (node (ref "U1") (pin "J8") (pinfunction "VCCPINT_J8") (pintype "power_in"))
      (node (ref "U1") (pin "K13") (pinfunction "VCCINT_K13") (pintype "power_in"))
      (node (ref "U1") (pin "L14") (pinfunction "VCCINT_L14") (pintype "power_in"))
      (node (ref "U1") (pin "L8") (pinfunction "VCCPINT_L8") (pintype "power_in"))
      (node (ref "U1") (pin "M13") (pinfunction "VCCINT_M13") (pintype "power_in"))
      (node (ref "U1") (pin "N14") (pinfunction "VCCINT_N14") (pintype "power_in"))
      (node (ref "U1") (pin "N8") (pinfunction "VCCPINT_N8") (pintype "power_in"))
      (node (ref "U1") (pin "P13") (pinfunction "VCCINT_P13") (pintype "power_in"))
      (node (ref "U1") (pin "R14") (pinfunction "VCCINT_R14") (pintype "power_in"))
      (node (ref "U1") (pin "R8") (pinfunction "VCCPINT_R8") (pintype "power_in"))
    )
    (net (code "2") (name "1.5V") (class "Default")
      (node (ref "C153") (pin "1") (pinfunction "1_1") (pintype "passive"))
      (node (ref "C154") (pin "1") (pinfunction "1_1") (pintype "passive"))
      (node (ref "C155") (pin "1") (pinfunction "1_1") (pintype "passive"))
      (node (ref "C156") (pin "1") (pinfunction "1_1") (pintype "passive"))
      (node (ref "C157") (pin "1") (pinfunction "1_1") (pintype "passive"))
      (node (ref "C158") (pin "1") (pinfunction "1_1") (pintype "passive"))
      (node (ref "C167") (pin "1") (pinfunction "1_1") (pintype "passive"))
      (node (ref "C168") (pin "1") (pinfunction "1_1") (pintype "passive"))
      (node (ref "C169") (pin "1") (pinfunction "1_1") (pintype "passive"))
      (node (ref "C170") (pin "1") (pinfunction "1_1") (pintype "passive"))
      (node (ref "C171") (pin "1") (pinfunction "1_1") (pintype "passive"))
      (node (ref "U1") (pin "E2") (pinfunction "VCCO_DDR_502_E2") (pintype "power_in"))
      (node (ref "U1") (pin "F5") (pinfunction "VCCO_DDR_502_F5") (pintype "power_in"))
      (node (ref "U1") (pin "H1") (pinfunction "VCCO_DDR_502_H1") (pintype "power_in"))
      (node (ref "U1") (pin "J4") (pinfunction "VCCO_DDR_502_J4") (pintype "power_in"))
      (node (ref "U1") (pin "K7") (pinfunction "VCCO_DDR_502_K7") (pintype "power_in"))
      (node (ref "U1") (pin "M3") (pinfunction "VCCO_DDR_502_M3") (pintype "power_in"))
      (node (ref "U1") (pin "N6") (pinfunction "VCCO_DDR_502_N6") (pintype "power_in"))
      (node (ref "U1") (pin "R2") (pinfunction "VCCO_DDR_502_R2") (pintype "power_in"))
      (node (ref "U1") (pin "V1") (pinfunction "VCCO_DDR_502_V1") (pintype "power_in"))
    )
    (net (code "3") (name "1.8V") (class "Default")
      (node (ref "C113") (pin "1") (pinfunction "1_1") (pintype "passive"))
      (node (ref "C114") (pin "1") (pinfunction "1_1") (pintype "passive"))
      (node (ref "C115") (pin "1") (pinfunction "1_1") (pintype "passive"))
      (node (ref "C116") (pin "1") (pinfunction "1_1") (pintype "passive"))
      (node (ref "C150") (pin "1") (pinfunction "1_1") (pintype "passive"))
      (node (ref "C151") (pin "1") (pinfunction "1_1") (pintype "passive"))
      (node (ref "C152") (pin "1") (pinfunction "1_1") (pintype "passive"))
      (node (ref "C164") (pin "1") (pinfunction "1_1") (pintype "passive"))
      (node (ref "C165") (pin "1") (pinfunction "1_1") (pintype "passive"))
      (node (ref "C166") (pin "1") (pinfunction "1_1") (pintype "passive"))
      (node (ref "C73") (pin "1") (pinfunction "1_1") (pintype "passive"))
      (node (ref "L3") (pin "2") (pinfunction "2_2") (pintype "passive"))
      (node (ref "L4") (pin "2") (pinfunction "2_2") (pintype "passive"))
      (node (ref "U1") (pin "G9") (pinfunction "VCCBATT_0_G9") (pintype "power_in"))
      (node (ref "U1") (pin "K9") (pinfunction "VCCPAUX_K9") (pintype "power_in"))
      (node (ref "U1") (pin "L10") (pinfunction "VCCAUX_L10") (pintype "power_in"))
      (node (ref "U1") (pin "M9") (pinfunction "VCCPAUX_M9") (pintype "power_in"))
      (node (ref "U1") (pin "N10") (pinfunction "VCCAUX_N10") (pintype "power_in"))
      (node (ref "U1") (pin "P11") (pinfunction "VCCAUX_P11") (pintype "power_in"))
      (node (ref "U1") (pin "P9") (pinfunction "VCCPAUX_P9") (pintype "power_in"))
      (node (ref "U1") (pin "R10") (pinfunction "VCCAUX_R10") (pintype "power_in"))
      (node (ref "U1") (pin "T9") (pinfunction "VCCPAUX_T9") (pintype "power_in"))
    )
    (net (code "4") (name "1.8VADC") (class "Default")
      (node (ref "C74") (pin "1") (pinfunction "1_1") (pintype "passive"))
      (node (ref "C75") (pin "1") (pinfunction "1_1") (pintype "passive"))
      (node (ref "L4") (pin "1") (pinfunction "1_1") (pintype "passive"))
      (node (ref "U1") (pin "K11") (pinfunction "VCCADC_0_K11") (pintype "power_in"))
    )
    (net (code "5") (name "1.8VPLL") (class "Default")
      (node (ref "C260") (pin "1") (pinfunction "1_1") (pintype "passive"))
      (node (ref "C72") (pin "1") (pinfunction "1_1") (pintype "passive"))
      (node (ref "L3") (pin "1") (pinfunction "1_1") (pintype "passive"))
      (node (ref "U1") (pin "H10") (pinfunction "VCCPLL_H10") (pintype "power_in"))
    )
    (net (code "6") (name "3.3V") (class "Default")
      (node (ref "C159") (pin "1") (pinfunction "1_1") (pintype "passive"))
      (node (ref "C84") (pin "1") (pinfunction "1_1") (pintype "passive"))
      (node (ref "C85") (pin "1") (pinfunction "1_1") (pintype "passive"))
      (node (ref "C86") (pin "1") (pinfunction "1_1") (pintype "passive"))
      (node (ref "C87") (pin "1") (pinfunction "1_1") (pintype "passive"))
      (node (ref "C88") (pin "1") (pinfunction "1_1") (pintype "passive"))
      (node (ref "C89") (pin "1") (pinfunction "1_1") (pintype "passive"))
      (node (ref "C90") (pin "1") (pinfunction "1_1") (pintype "passive"))
      (node (ref "C91") (pin "1") (pinfunction "1_1") (pintype "passive"))
      (node (ref "U1") (pin "A10") (pinfunction "VCCO_MIO1_501_A10") (pintype "power_in"))
      (node (ref "U1") (pin "B13") (pinfunction "VCCO_MIO1_501_B13") (pintype "power_in"))
      (node (ref "U1") (pin "B3") (pinfunction "VCCO_MIO0_500_B3") (pintype "power_in"))
      (node (ref "U1") (pin "C6") (pinfunction "VCCO_MIO0_500_C6") (pintype "power_in"))
      (node (ref "U1") (pin "D9") (pinfunction "VCCO_MIO1_501_D9") (pintype "power_in"))
      (node (ref "U1") (pin "E12") (pinfunction "VCCO_MIO1_501_E12") (pintype "power_in"))
      (node (ref "U1") (pin "R12") (pinfunction "VCCO_0_R12") (pintype "power_in"))
      (node (ref "U1") (pin "T10") (pinfunction "RSVDVCC3_T10") (pintype "power_in"))
      (node (ref "U1") (pin "T7") (pinfunction "RSVDVCC1_T7") (pintype "power_in"))
      (node (ref "U1") (pin "T8") (pinfunction "RSVDVCC2_T8") (pintype "power_in"))
    )
    (net (code "7") (name "GND") (class "Default")
      (node (ref "C100") (pin "2") (pinfunction "2_2") (pintype "passive"))
      (node (ref "C101") (pin "2") (pinfunction "2_2") (pintype "passive"))
      (node (ref "C102") (pin "2") (pinfunction "2_2") (pintype "passive"))
      (node (ref "C103") (pin "2") (pinfunction "2_2") (pintype "passive"))
      (node (ref "C104") (pin "2") (pinfunction "2_2") (pintype "passive"))
      (node (ref "C105") (pin "2") (pinfunction "2_2") (pintype "passive"))
      (node (ref "C106") (pin "2") (pinfunction "2_2") (pintype "passive"))
      (node (ref "C107") (pin "2") (pinfunction "2_2") (pintype "passive"))
      (node (ref "C108") (pin "2") (pinfunction "2_2") (pintype "passive"))
      (node (ref "C109") (pin "2") (pinfunction "2_2") (pintype "passive"))
      (node (ref "C110") (pin "2") (pinfunction "2_2") (pintype "passive"))
      (node (ref "C111") (pin "2") (pinfunction "2_2") (pintype "passive"))
      (node (ref "C112") (pin "2") (pinfunction "2_2") (pintype "passive"))
      (node (ref "C113") (pin "2") (pinfunction "2_2") (pintype "passive"))
      (node (ref "C114") (pin "2") (pinfunction "2_2") (pintype "passive"))
      (node (ref "C115") (pin "2") (pinfunction "2_2") (pintype "passive"))
      (node (ref "C116") (pin "2") (pinfunction "2_2") (pintype "passive"))
      (node (ref "C117") (pin "2") (pinfunction "2_2") (pintype "passive"))
      (node (ref "C118") (pin "2") (pinfunction "2_2") (pintype "passive"))
      (node (ref "C119") (pin "2") (pinfunction "2_2") (pintype "passive"))
      (node (ref "C120") (pin "2") (pinfunction "2_2") (pintype "passive"))
      (node (ref "C121") (pin "2") (pinfunction "2_2") (pintype "passive"))
      (node (ref "C122") (pin "2") (pinfunction "2_2") (pintype "passive"))
      (node (ref "C123") (pin "2") (pinfunction "2_2") (pintype "passive"))
      (node (ref "C124") (pin "2") (pinfunction "2_2") (pintype "passive"))
      (node (ref "C125") (pin "2") (pinfunction "2_2") (pintype "passive"))
      (node (ref "C126") (pin "2") (pinfunction "2_2") (pintype "passive"))
      (node (ref "C127") (pin "2") (pinfunction "2_2") (pintype "passive"))
      (node (ref "C128") (pin "2") (pinfunction "2_2") (pintype "passive"))
      (node (ref "C129") (pin "2") (pinfunction "2_2") (pintype "passive"))
      (node (ref "C130") (pin "2") (pinfunction "2_2") (pintype "passive"))
      (node (ref "C131") (pin "2") (pinfunction "2_2") (pintype "passive"))
      (node (ref "C132") (pin "2") (pinfunction "2_2") (pintype "passive"))
      (node (ref "C133") (pin "2") (pinfunction "2_2") (pintype "passive"))
      (node (ref "C134") (pin "2") (pinfunction "2_2") (pintype "passive"))
      (node (ref "C135") (pin "2") (pinfunction "2_2") (pintype "passive"))
      (node (ref "C136") (pin "2") (pinfunction "2_2") (pintype "passive"))
      (node (ref "C137") (pin "2") (pinfunction "2_2") (pintype "passive"))
      (node (ref "C138") (pin "2") (pinfunction "2_2") (pintype "passive"))
      (node (ref "C139") (pin "2") (pinfunction "2_2") (pintype "passive"))
      (node (ref "C140") (pin "2") (pinfunction "2_2") (pintype "passive"))
      (node (ref "C141") (pin "2") (pinfunction "2_2") (pintype "passive"))
      (node (ref "C142") (pin "2") (pinfunction "2_2") (pintype "passive"))
      (node (ref "C143") (pin "2") (pinfunction "2_2") (pintype "passive"))
      (node (ref "C144") (pin "2") (pinfunction "2_2") (pintype "passive"))
      (node (ref "C145") (pin "2") (pinfunction "2_2") (pintype "passive"))
      (node (ref "C146") (pin "2") (pinfunction "2_2") (pintype "passive"))
      (node (ref "C147") (pin "2") (pinfunction "2_2") (pintype "passive"))
      (node (ref "C148") (pin "2") (pinfunction "2_2") (pintype "passive"))
      (node (ref "C149") (pin "2") (pinfunction "2_2") (pintype "passive"))
      (node (ref "C150") (pin "2") (pinfunction "2_2") (pintype "passive"))
      (node (ref "C151") (pin "2") (pinfunction "2_2") (pintype "passive"))
      (node (ref "C152") (pin "2") (pinfunction "2_2") (pintype "passive"))
      (node (ref "C153") (pin "2") (pinfunction "2_2") (pintype "passive"))
      (node (ref "C154") (pin "2") (pinfunction "2_2") (pintype "passive"))
      (node (ref "C155") (pin "2") (pinfunction "2_2") (pintype "passive"))
      (node (ref "C156") (pin "2") (pinfunction "2_2") (pintype "passive"))
      (node (ref "C157") (pin "2") (pinfunction "2_2") (pintype "passive"))
      (node (ref "C158") (pin "2") (pinfunction "2_2") (pintype "passive"))
      (node (ref "C159") (pin "2") (pinfunction "2_2") (pintype "passive"))
      (node (ref "C160") (pin "2") (pinfunction "2_2") (pintype "passive"))
      (node (ref "C161") (pin "2") (pinfunction "2_2") (pintype "passive"))
      (node (ref "C162") (pin "2") (pinfunction "2_2") (pintype "passive"))
      (node (ref "C163") (pin "2") (pinfunction "2_2") (pintype "passive"))
      (node (ref "C164") (pin "2") (pinfunction "2_2") (pintype "passive"))
      (node (ref "C165") (pin "2") (pinfunction "2_2") (pintype "passive"))
      (node (ref "C166") (pin "2") (pinfunction "2_2") (pintype "passive"))
      (node (ref "C167") (pin "2") (pinfunction "2_2") (pintype "passive"))
      (node (ref "C168") (pin "2") (pinfunction "2_2") (pintype "passive"))
      (node (ref "C169") (pin "2") (pinfunction "2_2") (pintype "passive"))
      (node (ref "C170") (pin "2") (pinfunction "2_2") (pintype "passive"))
      (node (ref "C171") (pin "2") (pinfunction "2_2") (pintype "passive"))
      (node (ref "C260") (pin "2") (pinfunction "2_2") (pintype "passive"))
      (node (ref "C72") (pin "2") (pinfunction "2_2") (pintype "passive"))
      (node (ref "C73") (pin "2") (pinfunction "2_2") (pintype "passive"))
      (node (ref "C74") (pin "2") (pinfunction "2_2") (pintype "passive"))
      (node (ref "C75") (pin "2") (pinfunction "2_2") (pintype "passive"))
      (node (ref "C76") (pin "2") (pinfunction "2_2") (pintype "passive"))
      (node (ref "C77") (pin "2") (pinfunction "2_2") (pintype "passive"))
      (node (ref "C78") (pin "2") (pinfunction "2_2") (pintype "passive"))
      (node (ref "C79") (pin "2") (pinfunction "2_2") (pintype "passive"))
      (node (ref "C80") (pin "2") (pinfunction "2_2") (pintype "passive"))
      (node (ref "C81") (pin "2") (pinfunction "2_2") (pintype "passive"))
      (node (ref "C82") (pin "2") (pinfunction "2_2") (pintype "passive"))
      (node (ref "C83") (pin "2") (pinfunction "2_2") (pintype "passive"))
      (node (ref "C84") (pin "2") (pinfunction "2_2") (pintype "passive"))
      (node (ref "C85") (pin "2") (pinfunction "2_2") (pintype "passive"))
      (node (ref "C86") (pin "2") (pinfunction "2_2") (pintype "passive"))
      (node (ref "C87") (pin "2") (pinfunction "2_2") (pintype "passive"))
      (node (ref "C88") (pin "2") (pinfunction "2_2") (pintype "passive"))
      (node (ref "C89") (pin "2") (pinfunction "2_2") (pintype "passive"))
      (node (ref "C90") (pin "2") (pinfunction "2_2") (pintype "passive"))
      (node (ref "C91") (pin "2") (pinfunction "2_2") (pintype "passive"))
      (node (ref "C92") (pin "2") (pinfunction "2_2") (pintype "passive"))
      (node (ref "C93") (pin "2") (pinfunction "2_2") (pintype "passive"))
      (node (ref "C94") (pin "2") (pinfunction "2_2") (pintype "passive"))
      (node (ref "C95") (pin "2") (pinfunction "2_2") (pintype "passive"))
      (node (ref "C96") (pin "2") (pinfunction "2_2") (pintype "passive"))
      (node (ref "C97") (pin "2") (pinfunction "2_2") (pintype "passive"))
      (node (ref "C98") (pin "2") (pinfunction "2_2") (pintype "passive"))
      (node (ref "C99") (pin "2") (pinfunction "2_2") (pintype "passive"))
      (node (ref "U1") (pin "A15") (pinfunction "GND_A15") (pintype "power_in"))
      (node (ref "U1") (pin "A5") (pinfunction "GND_A5") (pintype "power_in"))
      (node (ref "U1") (pin "AA15") (pinfunction "GND_AA15") (pintype "power_in"))
      (node (ref "U1") (pin "AA5") (pinfunction "GND_AA5") (pintype "power_in"))
      (node (ref "U1") (pin "AB18") (pinfunction "GND_AB18") (pintype "power_in"))
      (node (ref "U1") (pin "AB8") (pinfunction "GND_AB8") (pintype "power_in"))
      (node (ref "U1") (pin "B18") (pinfunction "GND_B18") (pintype "power_in"))
      (node (ref "U1") (pin "B8") (pinfunction "GND_B8") (pintype "power_in"))
      (node (ref "U1") (pin "C1") (pinfunction "GND_C1") (pintype "power_in"))
      (node (ref "U1") (pin "C11") (pinfunction "GND_C11") (pintype "power_in"))
      (node (ref "U1") (pin "C21") (pinfunction "GND_C21") (pintype "power_in"))
      (node (ref "U1") (pin "D14") (pinfunction "GND_D14") (pintype "power_in"))
      (node (ref "U1") (pin "D4") (pinfunction "GND_D4") (pintype "power_in"))
      (node (ref "U1") (pin "E17") (pinfunction "GND_E17") (pintype "power_in"))
      (node (ref "U1") (pin "E7") (pinfunction "GND_E7") (pintype "power_in"))
      (node (ref "U1") (pin "F10") (pinfunction "GND_F10") (pintype "power_in"))
      (node (ref "U1") (pin "F20") (pinfunction "GND_F20") (pintype "power_in"))
      (node (ref "U1") (pin "G10") (pinfunction "RSVDGND_G10") (pintype "power_in"))
      (node (ref "U1") (pin "G3") (pinfunction "GND_G3") (pintype "power_in"))
      (node (ref "U1") (pin "H12") (pinfunction "GND_H12") (pintype "power_in"))
      (node (ref "U1") (pin "H14") (pinfunction "GND_H14") (pintype "power_in"))
      (node (ref "U1") (pin "H16") (pinfunction "GND_H16") (pintype "power_in"))
      (node (ref "U1") (pin "H6") (pinfunction "GND_H6") (pintype "power_in"))
      (node (ref "U1") (pin "H8") (pinfunction "GND_H8") (pintype "power_in"))
      (node (ref "U1") (pin "J11") (pinfunction "GND_J11") (pintype "power_in"))
      (node (ref "U1") (pin "J13") (pinfunction "GND_J13") (pintype "power_in"))
      (node (ref "U1") (pin "J19") (pinfunction "GND_J19") (pintype "power_in"))
      (node (ref "U1") (pin "J9") (pinfunction "GND_J9") (pintype "power_in"))
      (node (ref "U1") (pin "K10") (pinfunction "GND_K10") (pintype "power_in"))
      (node (ref "U1") (pin "K12") (pinfunction "GNDADC_0_K12") (pintype "power_in"))
      (node (ref "U1") (pin "K14") (pinfunction "GND_K14") (pintype "power_in"))
      (node (ref "U1") (pin "K2") (pinfunction "GND_K2") (pintype "power_in"))
      (node (ref "U1") (pin "K22") (pinfunction "GND_K22") (pintype "power_in"))
      (node (ref "U1") (pin "K8") (pinfunction "GND_K8") (pintype "power_in"))
      (node (ref "U1") (pin "L13") (pinfunction "GND_L13") (pintype "power_in"))
      (node (ref "U1") (pin "L15") (pinfunction "GND_L15") (pintype "power_in"))
      (node (ref "U1") (pin "L5") (pinfunction "GND_L5") (pintype "power_in"))
      (node (ref "U1") (pin "L9") (pinfunction "GND_L9") (pintype "power_in"))
      (node (ref "U1") (pin "M10") (pinfunction "GND_M10") (pintype "power_in"))
      (node (ref "U1") (pin "M14") (pinfunction "GND_M14") (pintype "power_in"))
      (node (ref "U1") (pin "M18") (pinfunction "GND_M18") (pintype "power_in"))
      (node (ref "U1") (pin "M8") (pinfunction "GND_M8") (pintype "power_in"))
      (node (ref "U1") (pin "N1") (pinfunction "GND_N1") (pintype "power_in"))
      (node (ref "U1") (pin "N13") (pinfunction "GND_N13") (pintype "power_in"))
      (node (ref "U1") (pin "N21") (pinfunction "GND_N21") (pintype "power_in"))
      (node (ref "U1") (pin "N9") (pinfunction "GND_N9") (pintype "power_in"))
      (node (ref "U1") (pin "P10") (pinfunction "GND_P10") (pintype "power_in"))
      (node (ref "U1") (pin "P12") (pinfunction "GND_P12") (pintype "power_in"))
      (node (ref "U1") (pin "P14") (pinfunction "GND_P14") (pintype "power_in"))
      (node (ref "U1") (pin "P4") (pinfunction "GND_P4") (pintype "power_in"))
      (node (ref "U1") (pin "P8") (pinfunction "GND_P8") (pintype "power_in"))
      (node (ref "U1") (pin "R11") (pinfunction "GND_R11") (pintype "power_in"))
      (node (ref "U1") (pin "R13") (pinfunction "GND_R13") (pintype "power_in"))
      (node (ref "U1") (pin "R17") (pinfunction "GND_R17") (pintype "power_in"))
      (node (ref "U1") (pin "R9") (pinfunction "GND_R9") (pintype "power_in"))
      (node (ref "U1") (pin "T20") (pinfunction "GND_T20") (pintype "power_in"))
      (node (ref "U1") (pin "U13") (pinfunction "GND_U13") (pintype "power_in"))
      (node (ref "U1") (pin "U3") (pinfunction "GND_U3") (pintype "power_in"))
      (node (ref "U1") (pin "V16") (pinfunction "GND_V16") (pintype "power_in"))
      (node (ref "U1") (pin "V6") (pinfunction "GND_V6") (pintype "power_in"))
      (node (ref "U1") (pin "W19") (pinfunction "GND_W19") (pintype "power_in"))
      (node (ref "U1") (pin "W9") (pinfunction "GND_W9") (pintype "power_in"))
      (node (ref "U1") (pin "Y12") (pinfunction "GND_Y12") (pintype "power_in"))
      (node (ref "U1") (pin "Y2") (pinfunction "GND_Y2") (pintype "power_in"))
      (node (ref "U1") (pin "Y22") (pinfunction "GND_Y22") (pintype "power_in"))
    )
    (net (code "8") (name "VCCO_13") (class "Default")
      (node (ref "C76") (pin "1") (pinfunction "1_1") (pintype "passive"))
      (node (ref "C77") (pin "1") (pinfunction "1_1") (pintype "passive"))
      (node (ref "C78") (pin "1") (pinfunction "1_1") (pintype "passive"))
      (node (ref "C79") (pin "1") (pinfunction "1_1") (pintype "passive"))
      (node (ref "C92") (pin "1") (pinfunction "1_1") (pintype "passive"))
      (node (ref "C93") (pin "1") (pinfunction "1_1") (pintype "passive"))
      (node (ref "C94") (pin "1") (pinfunction "1_1") (pintype "passive"))
      (node (ref "C95") (pin "1") (pinfunction "1_1") (pintype "passive"))
      (node (ref "C96") (pin "1") (pinfunction "1_1") (pintype "passive"))
      (node (ref "U1") (pin "AA10") (pinfunction "VCCO_13_AA10") (pintype "power_in"))
      (node (ref "U1") (pin "AB3") (pinfunction "VCCO_13_AB3") (pintype "power_in"))
      (node (ref "U1") (pin "T5") (pinfunction "VCCO_13_T5") (pintype "power_in"))
      (node (ref "U1") (pin "U8") (pinfunction "VCCO_13_U8") (pintype "power_in"))
      (node (ref "U1") (pin "V11") (pinfunction "VCCO_13_V11") (pintype "power_in"))
      (node (ref "U1") (pin "W4") (pinfunction "VCCO_13_W4") (pintype "power_in"))
      (node (ref "U1") (pin "Y7") (pinfunction "VCCO_13_Y7") (pintype "power_in"))
    )
    (net (code "9") (name "VCCO_33") (class "Default")
      (node (ref "C117") (pin "1") (pinfunction "1_1") (pintype "passive"))
      (node (ref "C118") (pin "1") (pinfunction "1_1") (pintype "passive"))
      (node (ref "C119") (pin "1") (pinfunction "1_1") (pintype "passive"))
      (node (ref "C120") (pin "1") (pinfunction "1_1") (pintype "passive"))
      (node (ref "C135") (pin "1") (pinfunction "1_1") (pintype "passive"))
      (node (ref "C136") (pin "1") (pinfunction "1_1") (pintype "passive"))
      (node (ref "C137") (pin "1") (pinfunction "1_1") (pintype "passive"))
      (node (ref "C138") (pin "1") (pinfunction "1_1") (pintype "passive"))
      (node (ref "C139") (pin "1") (pinfunction "1_1") (pintype "passive"))
      (node (ref "U1") (pin "AA20") (pinfunction "VCCO_33_AA20") (pintype "power_in"))
      (node (ref "U1") (pin "AB13") (pinfunction "VCCO_33_AB13") (pintype "power_in"))
      (node (ref "U1") (pin "U18") (pinfunction "VCCO_33_U18") (pintype "power_in"))
      (node (ref "U1") (pin "V21") (pinfunction "VCCO_33_V21") (pintype "power_in"))
      (node (ref "U1") (pin "W14") (pinfunction "VCCO_33_W14") (pintype "power_in"))
      (node (ref "U1") (pin "Y17") (pinfunction "VCCO_33_Y17") (pintype "power_in"))
    )
    (net (code "10") (name "VCCO_34") (class "Default")
      (node (ref "C100") (pin "1") (pinfunction "1_1") (pintype "passive"))
      (node (ref "C101") (pin "1") (pinfunction "1_1") (pintype "passive"))
      (node (ref "C80") (pin "1") (pinfunction "1_1") (pintype "passive"))
      (node (ref "C81") (pin "1") (pinfunction "1_1") (pintype "passive"))
      (node (ref "C82") (pin "1") (pinfunction "1_1") (pintype "passive"))
      (node (ref "C83") (pin "1") (pinfunction "1_1") (pintype "passive"))
      (node (ref "C97") (pin "1") (pinfunction "1_1") (pintype "passive"))
      (node (ref "C98") (pin "1") (pinfunction "1_1") (pintype "passive"))
      (node (ref "C99") (pin "1") (pinfunction "1_1") (pintype "passive"))
      (node (ref "U1") (pin "K17") (pinfunction "VCCO_34_K17") (pintype "power_in"))
      (node (ref "U1") (pin "L20") (pinfunction "VCCO_34_L20") (pintype "power_in"))
      (node (ref "U1") (pin "N16") (pinfunction "VCCO_34_N16") (pintype "power_in"))
      (node (ref "U1") (pin "P19") (pinfunction "VCCO_34_P19") (pintype "power_in"))
      (node (ref "U1") (pin "R22") (pinfunction "VCCO_34_R22") (pintype "power_in"))
      (node (ref "U1") (pin "T15") (pinfunction "VCCO_34_T15") (pintype "power_in"))
    )
    (net (code "11") (name "VCCO_35") (class "Default")
      (node (ref "C121") (pin "1") (pinfunction "1_1") (pintype "passive"))
      (node (ref "C122") (pin "1") (pinfunction "1_1") (pintype "passive"))
      (node (ref "C123") (pin "1") (pinfunction "1_1") (pintype "passive"))
      (node (ref "C124") (pin "1") (pinfunction "1_1") (pintype "passive"))
      (node (ref "C140") (pin "1") (pinfunction "1_1") (pintype "passive"))
      (node (ref "C141") (pin "1") (pinfunction "1_1") (pintype "passive"))
      (node (ref "C142") (pin "1") (pinfunction "1_1") (pintype "passive"))
      (node (ref "C143") (pin "1") (pinfunction "1_1") (pintype "passive"))
      (node (ref "C144") (pin "1") (pinfunction "1_1") (pintype "passive"))
      (node (ref "U1") (pin "A20") (pinfunction "VCCO_35_A20") (pintype "power_in"))
      (node (ref "U1") (pin "C16") (pinfunction "VCCO_35_C16") (pintype "power_in"))
      (node (ref "U1") (pin "D19") (pinfunction "VCCO_35_D19") (pintype "power_in"))
      (node (ref "U1") (pin "E22") (pinfunction "VCCO_35_E22") (pintype "power_in"))
      (node (ref "U1") (pin "F15") (pinfunction "VCCO_35_F15") (pintype "power_in"))
      (node (ref "U1") (pin "G18") (pinfunction "VCCO_35_G18") (pintype "power_in"))
      (node (ref "U1") (pin "H21") (pinfunction "VCCO_35_H21") (pintype "power_in"))
    )
  )
)
